# AUTOMATIC_WATER_PUMPS_V1.net
KiCad netlist of a schematic drawn in Altium Designer
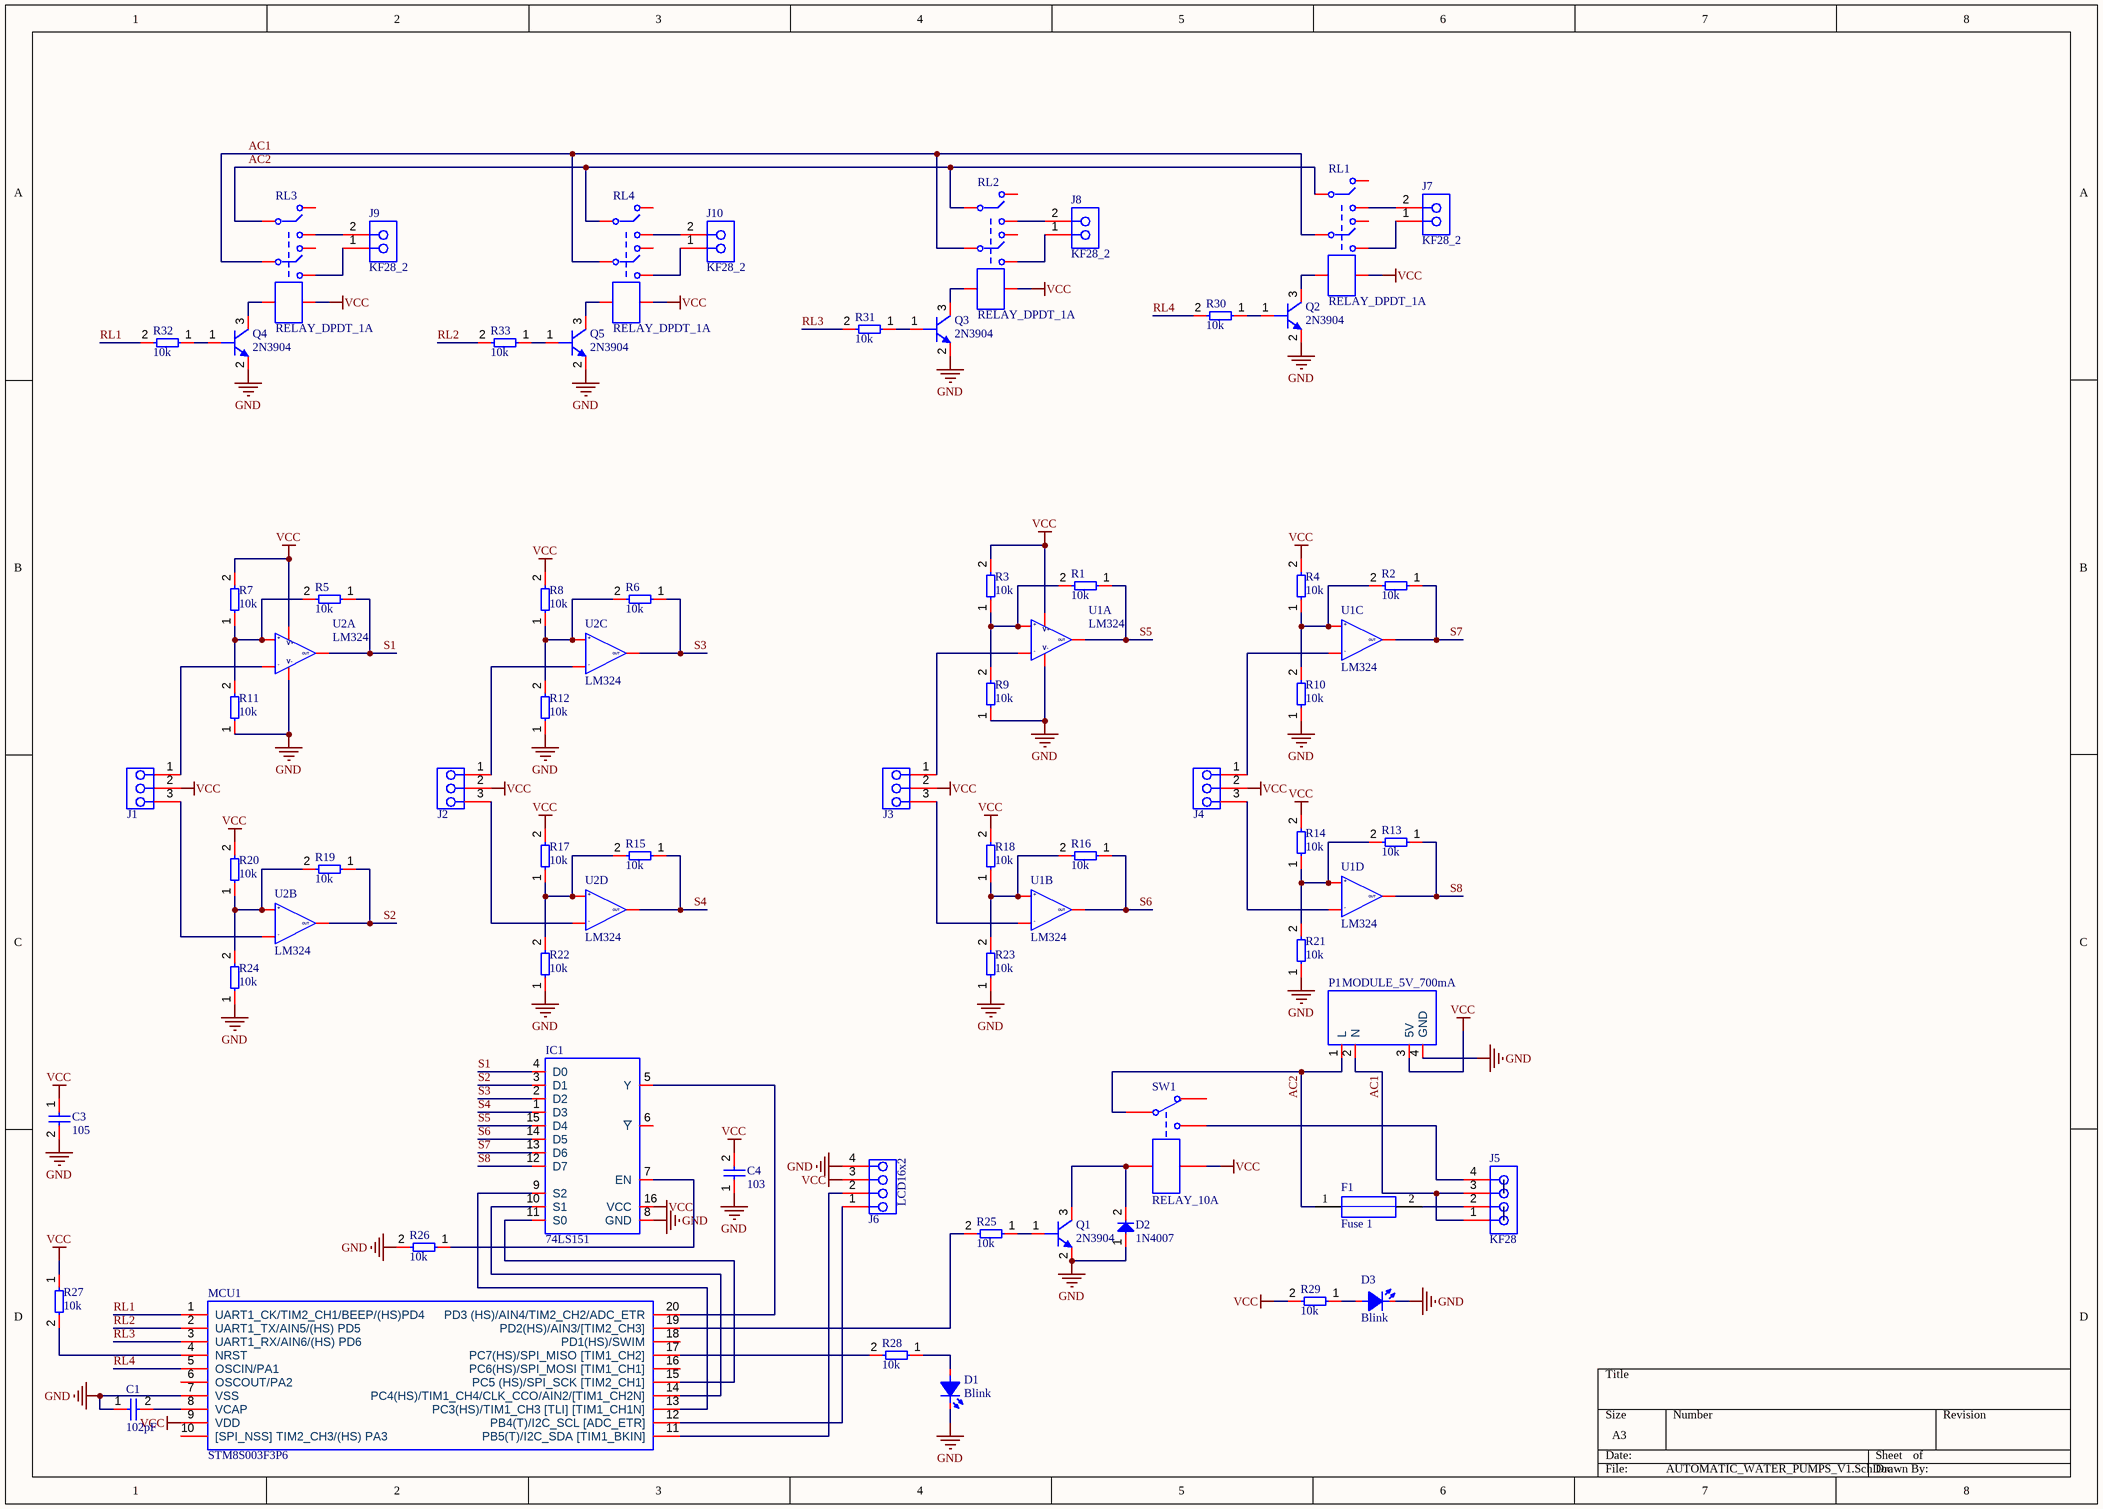
[diagram p0: AUTOMATIC_WATER_PUMPS_V1.SchDoc]

(export (version "E")
  (design (tool "Eeschema 10.0.6"))
  (components
    (comp (ref "C1")
      (value "102pF")
      (footprint "C0805")
      (libsource (lib "Lib31082020") (part "Capacitors(SMD)"))
    )
    (comp (ref "C3") (value "105") (footprint "C0805") (libsource (lib "Lib31082020") (part "C0805")))
    (comp (ref "C4") (value "103") (footprint "C0805") (libsource (lib "Lib31082020") (part "C0805")))
    (comp (ref "D1") (value "Blink") (footprint "L0805RED") (libsource (lib "Lib31082020") (part "LED0805")))
    (comp (ref "D2")
      (value "1N4007")
      (footprint "DO-214AC(SMA)")
      (libsource (lib "Lib31082020") (part "Diode 1N4007-DO214AC(SMA)"))
    )
    (comp (ref "D3") (value "Blink") (footprint "L0805RED") (libsource (lib "Lib31082020") (part "LED0805")))
    (comp (ref "F1")
      (value "Fuse 1")
      (footprint "FUSE2")
      (fields (field (name "PUBLISHER") "Altium Limited"))
      (libsource (lib "Library 3D") (part "Fuse 1"))
    )
    (comp (ref "IC1")
      (value "74LS151")
      (footprint "SOP16")
      (description "8-input multiplexer")
      (libsource (lib "Lib31082020") (part "74LS151"))
    )
    (comp (ref "J1")
      (value "WT1")
      (footprint "JST - XH - Thru (R) - 3Pin - 2.54mm")
      (libsource (lib "Lib31082020") (part "JST - XH - Thru (R) - 3Pin - 2.54mm"))
    )
    (comp (ref "J2")
      (value "WT2")
      (footprint "JST - XH - Thru (R) - 3Pin - 2.54mm")
      (libsource (lib "Lib31082020") (part "JST - XH - Thru (R) - 3Pin - 2.54mm"))
    )
    (comp (ref "J3")
      (value "WT3")
      (footprint "JST - XH - Thru (R) - 3Pin - 2.54mm")
      (libsource (lib "Lib31082020") (part "JST - XH - Thru (R) - 3Pin - 2.54mm"))
    )
    (comp (ref "J4")
      (value "WT4")
      (footprint "JST - XH - Thru (R) - 3Pin - 2.54mm")
      (libsource (lib "Lib31082020") (part "JST - XH - Thru (R) - 3Pin - 2.54mm"))
    )
    (comp (ref "J5")
      (value "KF28")
      (footprint "HEADER_KF128_4_5.08MM")
      (libsource (lib "Lib31082020") (part "HEADER_KF128_4_5.08MM"))
    )
    (comp (ref "J6")
      (value "LCD16x2")
      (footprint "JST - XH - Thru (R) - 4Pin - 2.54mm")
      (libsource (lib "Lib31082020") (part "JST - XH - Thru (R) - 4Pin - 2.54mm"))
    )
    (comp (ref "J7")
      (value "KF28_2")
      (footprint "HEADER_KF128_2_5.08MM")
      (libsource (lib "Lib31082020") (part "HEADER_KF128_2_5.08MM"))
    )
    (comp (ref "J8")
      (value "KF28_2")
      (footprint "HEADER_KF128_2_5.08MM")
      (libsource (lib "Lib31082020") (part "HEADER_KF128_2_5.08MM"))
    )
    (comp (ref "J9")
      (value "KF28_2")
      (footprint "HEADER_KF128_2_5.08MM")
      (libsource (lib "Lib31082020") (part "HEADER_KF128_2_5.08MM"))
    )
    (comp (ref "J10")
      (value "KF28_2")
      (footprint "HEADER_KF128_2_5.08MM")
      (libsource (lib "Lib31082020") (part "HEADER_KF128_2_5.08MM"))
    )
    (comp (ref "MCU1")
      (value "STM8S003F3P6")
      (footprint "TSSOP20_0.65_4.4")
      (libsource (lib "Lib31082020") (part "STM8S003F3P6"))
    )
    (comp (ref "P1")
      (value "MODULE_5V_700mA")
      (footprint "MODULE_5V_700mA")
      (libsource (lib "Lib31082020") (part "MODULE_5V_700mA"))
    )
    (comp (ref "Q1")
      (value "2N3904")
      (footprint "SOT23-3")
      (libsource (lib "Lib31082020") (part "2N3904 (SOT-23)"))
    )
    (comp (ref "Q2")
      (value "2N3904")
      (footprint "SOT23-3")
      (libsource (lib "Lib31082020") (part "2N3904 (SOT-23)"))
    )
    (comp (ref "Q3")
      (value "2N3904")
      (footprint "SOT23-3")
      (libsource (lib "Lib31082020") (part "2N3904 (SOT-23)"))
    )
    (comp (ref "Q4")
      (value "2N3904")
      (footprint "SOT23-3")
      (libsource (lib "Lib31082020") (part "2N3904 (SOT-23)"))
    )
    (comp (ref "Q5")
      (value "2N3904")
      (footprint "SOT23-3")
      (libsource (lib "Lib31082020") (part "2N3904 (SOT-23)"))
    )
    (comp (ref "R1") (value "10k") (footprint "R0805") (libsource (lib "Lib31082020") (part "Resistor SMD")))
    (comp (ref "R2") (value "10k") (footprint "R0805") (libsource (lib "Lib31082020") (part "Resistor SMD")))
    (comp (ref "R3") (value "10k") (footprint "R0805") (libsource (lib "") (part "Resistor SMD_1")))
    (comp (ref "R4") (value "10k") (footprint "R0805") (libsource (lib "") (part "Resistor SMD_1")))
    (comp (ref "R5") (value "10k") (footprint "R0805") (libsource (lib "Lib31082020") (part "Resistor SMD")))
    (comp (ref "R6") (value "10k") (footprint "R0805") (libsource (lib "Lib31082020") (part "Resistor SMD")))
    (comp (ref "R7") (value "10k") (footprint "R0805") (libsource (lib "") (part "Resistor SMD_1")))
    (comp (ref "R8") (value "10k") (footprint "R0805") (libsource (lib "") (part "Resistor SMD_1")))
    (comp (ref "R9") (value "10k") (footprint "R0805") (libsource (lib "") (part "Resistor SMD_1")))
    (comp (ref "R10") (value "10k") (footprint "R0805") (libsource (lib "") (part "Resistor SMD_1")))
    (comp (ref "R11") (value "10k") (footprint "R0805") (libsource (lib "") (part "Resistor SMD_1")))
    (comp (ref "R12") (value "10k") (footprint "R0805") (libsource (lib "") (part "Resistor SMD_1")))
    (comp (ref "R13") (value "10k") (footprint "R0805") (libsource (lib "Lib31082020") (part "Resistor SMD")))
    (comp (ref "R14") (value "10k") (footprint "R0805") (libsource (lib "") (part "Resistor SMD_1")))
    (comp (ref "R15") (value "10k") (footprint "R0805") (libsource (lib "Lib31082020") (part "Resistor SMD")))
    (comp (ref "R16") (value "10k") (footprint "R0805") (libsource (lib "Lib31082020") (part "Resistor SMD")))
    (comp (ref "R17") (value "10k") (footprint "R0805") (libsource (lib "") (part "Resistor SMD_1")))
    (comp (ref "R18") (value "10k") (footprint "R0805") (libsource (lib "") (part "Resistor SMD_1")))
    (comp (ref "R19") (value "10k") (footprint "R0805") (libsource (lib "Lib31082020") (part "Resistor SMD")))
    (comp (ref "R20") (value "10k") (footprint "R0805") (libsource (lib "") (part "Resistor SMD_1")))
    (comp (ref "R21") (value "10k") (footprint "R0805") (libsource (lib "") (part "Resistor SMD_1")))
    (comp (ref "R22") (value "10k") (footprint "R0805") (libsource (lib "") (part "Resistor SMD_1")))
    (comp (ref "R23") (value "10k") (footprint "R0805") (libsource (lib "") (part "Resistor SMD_1")))
    (comp (ref "R24") (value "10k") (footprint "R0805") (libsource (lib "") (part "Resistor SMD_1")))
    (comp (ref "R25") (value "10k") (footprint "R0805") (libsource (lib "Lib31082020") (part "Resistor SMD")))
    (comp (ref "R26") (value "10k") (footprint "R0805") (libsource (lib "Lib31082020") (part "Resistor SMD")))
    (comp (ref "R27") (value "10k") (footprint "R0805") (libsource (lib "") (part "Resistor SMD_2")))
    (comp (ref "R28") (value "10k") (footprint "R0805") (libsource (lib "Lib31082020") (part "Resistor SMD")))
    (comp (ref "R29") (value "10k") (footprint "R0805") (libsource (lib "Lib31082020") (part "Resistor SMD")))
    (comp (ref "R30") (value "10k") (footprint "R0805") (libsource (lib "Lib31082020") (part "Resistor SMD")))
    (comp (ref "R31") (value "10k") (footprint "R0805") (libsource (lib "Lib31082020") (part "Resistor SMD")))
    (comp (ref "R32") (value "10k") (footprint "R0805") (libsource (lib "Lib31082020") (part "Resistor SMD")))
    (comp (ref "R33") (value "10k") (footprint "R0805") (libsource (lib "Lib31082020") (part "Resistor SMD")))
    (comp (ref "RL1")
      (value "RELAY_DPDT_1A")
      (footprint "RELAY_DPDT_1A")
      (libsource (lib "Lib31082020") (part "RELAY_DPDT_1A"))
    )
    (comp (ref "RL2")
      (value "RELAY_DPDT_1A")
      (footprint "RELAY_DPDT_1A")
      (libsource (lib "Lib31082020") (part "RELAY_DPDT_1A"))
    )
    (comp (ref "RL3")
      (value "RELAY_DPDT_1A")
      (footprint "RELAY_DPDT_1A")
      (libsource (lib "Lib31082020") (part "RELAY_DPDT_1A"))
    )
    (comp (ref "RL4")
      (value "RELAY_DPDT_1A")
      (footprint "RELAY_DPDT_1A")
      (libsource (lib "Lib31082020") (part "RELAY_DPDT_1A"))
    )
    (comp (ref "SW1")
      (value "RELAY_10A")
      (footprint "RELAY_10A_5PIN")
      (libsource (lib "Lib31082020") (part "RELAY_10A"))
    )
    (comp (ref "U1")
      (value "LM324")
      (footprint "SOP-14")
      (description "Quad-Operational Amp")
      (libsource (lib "Lib31082020") (part "LM324"))
    )
    (comp (ref "U2")
      (value "LM324")
      (footprint "SOP-14")
      (description "Quad-Operational Amp")
      (libsource (lib "Lib31082020") (part "LM324"))
    )
  )
  (nets
    (net (code "1") (name "/AC1") (class "Default")
      (node (ref "J5") (pin "1") (pinfunction "1_1") (pintype "passive"))
      (node (ref "J5") (pin "3") (pinfunction "3_3") (pintype "passive"))
      (node (ref "P1") (pin "2") (pinfunction "N_2") (pintype "passive"))
      (node (ref "RL1") (pin "5") (pinfunction "5_5") (pintype "passive"))
      (node (ref "RL2") (pin "5") (pinfunction "5_5") (pintype "passive"))
      (node (ref "RL3") (pin "5") (pinfunction "5_5") (pintype "passive"))
      (node (ref "RL4") (pin "5") (pinfunction "5_5") (pintype "passive"))
    )
    (net (code "2") (name "/AC2") (class "Default")
      (node (ref "F1") (pin "1") (pinfunction "1_1") (pintype "passive"))
      (node (ref "P1") (pin "1") (pinfunction "L_1") (pintype "passive"))
      (node (ref "RL1") (pin "2") (pinfunction "2_2") (pintype "passive"))
      (node (ref "RL2") (pin "2") (pinfunction "2_2") (pintype "passive"))
      (node (ref "RL3") (pin "2") (pinfunction "2_2") (pintype "passive"))
      (node (ref "RL4") (pin "2") (pinfunction "2_2") (pintype "passive"))
      (node (ref "SW1") (pin "2") (pinfunction "2_2") (pintype "passive"))
    )
    (net (code "3") (name "/RL1") (class "Default")
      (node (ref "MCU1") (pin "1") (pinfunction "UART1_CK/TIM2_CH1/BEEP/(HS)PD4_1") (pintype "passive"))
      (node (ref "R32") (pin "2") (pinfunction "2_2") (pintype "passive"))
    )
    (net (code "4") (name "/RL2") (class "Default")
      (node (ref "MCU1") (pin "2") (pinfunction "UART1_TX/AIN5/(HS)_PD5_2") (pintype "passive"))
      (node (ref "R33") (pin "2") (pinfunction "2_2") (pintype "passive"))
    )
    (net (code "5") (name "/RL3") (class "Default")
      (node (ref "MCU1") (pin "3") (pinfunction "UART1_RX/AIN6/(HS)_PD6_3") (pintype "passive"))
      (node (ref "R31") (pin "2") (pinfunction "2_2") (pintype "passive"))
    )
    (net (code "6") (name "/RL4") (class "Default")
      (node (ref "MCU1") (pin "5") (pinfunction "OSCIN/PA1_5") (pintype "passive"))
      (node (ref "R30") (pin "2") (pinfunction "2_2") (pintype "passive"))
    )
    (net (code "7") (name "/S1") (class "Default")
      (node (ref "IC1") (pin "4") (pinfunction "D0_4") (pintype "passive"))
      (node (ref "R5") (pin "1") (pinfunction "1_1") (pintype "passive"))
      (node (ref "U2") (pin "1") (pinfunction "OUT_1") (pintype "passive"))
    )
    (net (code "8") (name "/S2") (class "Default")
      (node (ref "IC1") (pin "3") (pinfunction "D1_3") (pintype "passive"))
      (node (ref "R19") (pin "1") (pinfunction "1_1") (pintype "passive"))
      (node (ref "U2") (pin "7") (pinfunction "OUT_7") (pintype "passive"))
    )
    (net (code "9") (name "/S3") (class "Default")
      (node (ref "IC1") (pin "2") (pinfunction "D2_2") (pintype "passive"))
      (node (ref "R6") (pin "1") (pinfunction "1_1") (pintype "passive"))
      (node (ref "U2") (pin "8") (pinfunction "OUT_8") (pintype "passive"))
    )
    (net (code "10") (name "/S4") (class "Default")
      (node (ref "IC1") (pin "1") (pinfunction "D3_1") (pintype "passive"))
      (node (ref "R15") (pin "1") (pinfunction "1_1") (pintype "passive"))
      (node (ref "U2") (pin "14") (pinfunction "OUT_14") (pintype "passive"))
    )
    (net (code "11") (name "/S5") (class "Default")
      (node (ref "IC1") (pin "15") (pinfunction "D4_15") (pintype "passive"))
      (node (ref "R1") (pin "1") (pinfunction "1_1") (pintype "passive"))
      (node (ref "U1") (pin "1") (pinfunction "OUT_1") (pintype "passive"))
    )
    (net (code "12") (name "/S6") (class "Default")
      (node (ref "IC1") (pin "14") (pinfunction "D5_14") (pintype "passive"))
      (node (ref "R16") (pin "1") (pinfunction "1_1") (pintype "passive"))
      (node (ref "U1") (pin "7") (pinfunction "OUT_7") (pintype "passive"))
    )
    (net (code "13") (name "/S7") (class "Default")
      (node (ref "IC1") (pin "13") (pinfunction "D6_13") (pintype "passive"))
      (node (ref "R2") (pin "1") (pinfunction "1_1") (pintype "passive"))
      (node (ref "U1") (pin "8") (pinfunction "OUT_8") (pintype "passive"))
    )
    (net (code "14") (name "/S8") (class "Default")
      (node (ref "IC1") (pin "12") (pinfunction "D7_12") (pintype "passive"))
      (node (ref "R13") (pin "1") (pinfunction "1_1") (pintype "passive"))
      (node (ref "U1") (pin "14") (pinfunction "OUT_14") (pintype "passive"))
    )
    (net (code "15") (name "GND") (class "Default")
      (node (ref "C1") (pin "1") (pinfunction "1_1") (pintype "passive"))
      (node (ref "C3") (pin "2") (pinfunction "2_2") (pintype "passive"))
      (node (ref "C4") (pin "1") (pinfunction "1_1") (pintype "passive"))
      (node (ref "D1") (pin "2") (pinfunction "K_2") (pintype "passive"))
      (node (ref "D2") (pin "1") (pinfunction "1_1") (pintype "passive"))
      (node (ref "D3") (pin "2") (pinfunction "K_2") (pintype "passive"))
      (node (ref "IC1") (pin "8") (pinfunction "GND_8") (pintype "passive"))
      (node (ref "J6") (pin "4") (pinfunction "4_4") (pintype "passive"))
      (node (ref "MCU1") (pin "7") (pinfunction "VSS_7") (pintype "passive"))
      (node (ref "P1") (pin "4") (pinfunction "GND_4") (pintype "passive"))
      (node (ref "Q1") (pin "2") (pinfunction "E_2") (pintype "passive"))
      (node (ref "Q2") (pin "2") (pinfunction "E_2") (pintype "passive"))
      (node (ref "Q3") (pin "2") (pinfunction "E_2") (pintype "passive"))
      (node (ref "Q4") (pin "2") (pinfunction "E_2") (pintype "passive"))
      (node (ref "Q5") (pin "2") (pinfunction "E_2") (pintype "passive"))
      (node (ref "R10") (pin "1") (pinfunction "1_1") (pintype "passive"))
      (node (ref "R11") (pin "1") (pinfunction "1_1") (pintype "passive"))
      (node (ref "R12") (pin "1") (pinfunction "1_1") (pintype "passive"))
      (node (ref "R21") (pin "1") (pinfunction "1_1") (pintype "passive"))
      (node (ref "R22") (pin "1") (pinfunction "1_1") (pintype "passive"))
      (node (ref "R23") (pin "1") (pinfunction "1_1") (pintype "passive"))
      (node (ref "R24") (pin "1") (pinfunction "1_1") (pintype "passive"))
      (node (ref "R26") (pin "2") (pinfunction "2_2") (pintype "passive"))
      (node (ref "R9") (pin "1") (pinfunction "1_1") (pintype "passive"))
      (node (ref "U1") (pin "11") (pinfunction "11_11") (pintype "power_in"))
      (node (ref "U2") (pin "11") (pinfunction "11_11") (pintype "power_in"))
    )
    (net (code "16") (name "Net-(D1-A)") (class "Default")
      (node (ref "D1") (pin "1") (pinfunction "A_1") (pintype "passive"))
      (node (ref "R28") (pin "1") (pinfunction "1_1") (pintype "passive"))
    )
    (net (code "17") (name "Net-(D3-A)") (class "Default")
      (node (ref "D3") (pin "1") (pinfunction "A_1") (pintype "passive"))
      (node (ref "R29") (pin "1") (pinfunction "1_1") (pintype "passive"))
    )
    (net (code "18") (name "Net-(F1-Pad2)") (class "Default")
      (node (ref "F1") (pin "2") (pinfunction "2_2") (pintype "passive"))
      (node (ref "J5") (pin "2") (pinfunction "2_2") (pintype "passive"))
    )
    (net (code "19") (name "Net-(IC1-EN)") (class "Default")
      (node (ref "IC1") (pin "7") (pinfunction "EN_7") (pintype "passive"))
      (node (ref "R26") (pin "1") (pinfunction "1_1") (pintype "passive"))
    )
    (net (code "20") (name "Net-(IC1-S0)") (class "Default")
      (node (ref "IC1") (pin "11") (pinfunction "S0_11") (pintype "passive"))
      (node (ref "MCU1") (pin "15") (pinfunction "PC5_(HS)/SPI_SCK_[TIM2_CH1]_15") (pintype "passive"))
    )
    (net (code "21") (name "Net-(IC1-S1)") (class "Default")
      (node (ref "IC1") (pin "10") (pinfunction "S1_10") (pintype "passive"))
      (node (ref "MCU1") (pin "14") (pinfunction "PC4(HS)/TIM1_CH4/CLK_CCO/AIN2/[TIM1_CH2N]_14") (pintype "passive"))
    )
    (net (code "22") (name "Net-(IC1-S2)") (class "Default")
      (node (ref "IC1") (pin "9") (pinfunction "S2_9") (pintype "passive"))
      (node (ref "MCU1") (pin "13") (pinfunction "PC3(HS)/TIM1_CH3_[TLI]_[TIM1_CH1N]_13") (pintype "passive"))
    )
    (net (code "23") (name "Net-(IC1-Y)") (class "Default")
      (node (ref "IC1") (pin "5") (pinfunction "Y_5") (pintype "passive"))
      (node (ref "MCU1") (pin "20") (pinfunction "PD3_(HS)/AIN4/TIM2_CH2/ADC_ETR_20") (pintype "passive"))
    )
    (net (code "24") (name "Net-(J5-Pad4)") (class "Default")
      (node (ref "J5") (pin "4") (pinfunction "4_4") (pintype "passive"))
      (node (ref "SW1") (pin "5") (pinfunction "5_5") (pintype "passive"))
    )
    (net (code "25") (name "Net-(J7-Pad1)") (class "Default")
      (node (ref "J7") (pin "1") (pinfunction "1_1") (pintype "passive"))
      (node (ref "RL1") (pin "6") (pinfunction "6_6") (pintype "passive"))
    )
    (net (code "26") (name "Net-(J7-Pad2)") (class "Default")
      (node (ref "J7") (pin "2") (pinfunction "2_2") (pintype "passive"))
      (node (ref "RL1") (pin "3") (pinfunction "3_3") (pintype "passive"))
    )
    (net (code "27") (name "Net-(J8-Pad1)") (class "Default")
      (node (ref "J8") (pin "1") (pinfunction "1_1") (pintype "passive"))
      (node (ref "RL2") (pin "6") (pinfunction "6_6") (pintype "passive"))
    )
    (net (code "28") (name "Net-(J8-Pad2)") (class "Default")
      (node (ref "J8") (pin "2") (pinfunction "2_2") (pintype "passive"))
      (node (ref "RL2") (pin "3") (pinfunction "3_3") (pintype "passive"))
    )
    (net (code "29") (name "Net-(J9-Pad1)") (class "Default")
      (node (ref "J9") (pin "1") (pinfunction "1_1") (pintype "passive"))
      (node (ref "RL3") (pin "6") (pinfunction "6_6") (pintype "passive"))
    )
    (net (code "30") (name "Net-(J9-Pad2)") (class "Default")
      (node (ref "J9") (pin "2") (pinfunction "2_2") (pintype "passive"))
      (node (ref "RL3") (pin "3") (pinfunction "3_3") (pintype "passive"))
    )
    (net (code "31") (name "Net-(J10-Pad1)") (class "Default")
      (node (ref "J10") (pin "1") (pinfunction "1_1") (pintype "passive"))
      (node (ref "RL4") (pin "6") (pinfunction "6_6") (pintype "passive"))
    )
    (net (code "32") (name "Net-(J10-Pad2)") (class "Default")
      (node (ref "J10") (pin "2") (pinfunction "2_2") (pintype "passive"))
      (node (ref "RL4") (pin "3") (pinfunction "3_3") (pintype "passive"))
    )
    (net (code "33") (name "Net-(MCU1-NRST)") (class "Default")
      (node (ref "MCU1") (pin "4") (pinfunction "NRST_4") (pintype "passive"))
      (node (ref "R27") (pin "2") (pinfunction "2_2") (pintype "passive"))
    )
    (net (code "34") (name "Net-(MCU1-PB4(T){slash}I2C_SCL_[ADC_ETR])") (class "Default")
      (node (ref "J6") (pin "1") (pinfunction "1_1") (pintype "passive"))
      (node (ref "MCU1") (pin "12") (pinfunction "PB4(T)/I2C_SCL_[ADC_ETR]_12") (pintype "passive"))
    )
    (net (code "35") (name "Net-(MCU1-PB5(T){slash}I2C_SDA_[TIM1_BKIN])") (class "Default")
      (node (ref "J6") (pin "2") (pinfunction "2_2") (pintype "passive"))
      (node (ref "MCU1") (pin "11") (pinfunction "PB5(T)/I2C_SDA_[TIM1_BKIN]_11") (pintype "passive"))
    )
    (net (code "36") (name "Net-(MCU1-PC7(HS){slash}SPI_MISO_[TIM1_CH2])") (class "Default")
      (node (ref "MCU1") (pin "17") (pinfunction "PC7(HS)/SPI_MISO_[TIM1_CH2]_17") (pintype "passive"))
      (node (ref "R28") (pin "2") (pinfunction "2_2") (pintype "passive"))
    )
    (net (code "37") (name "Net-(MCU1-PD2(HS){slash}AIN3{slash}[TIM2_CH3])") (class "Default")
      (node (ref "MCU1") (pin "19") (pinfunction "PD2(HS)/AIN3/[TIM2_CH3]_19") (pintype "passive"))
      (node (ref "R25") (pin "2") (pinfunction "2_2") (pintype "passive"))
    )
    (net (code "38") (name "Net-(MCU1-VCAP)") (class "Default")
      (node (ref "C1") (pin "2") (pinfunction "2_2") (pintype "passive"))
      (node (ref "MCU1") (pin "8") (pinfunction "VCAP_8") (pintype "passive"))
    )
    (net (code "39") (name "Net-(Q1-B)") (class "Default")
      (node (ref "Q1") (pin "1") (pinfunction "B_1") (pintype "passive"))
      (node (ref "R25") (pin "1") (pinfunction "1_1") (pintype "passive"))
    )
    (net (code "40") (name "Net-(Q1-C)") (class "Default")
      (node (ref "D2") (pin "2") (pinfunction "2_2") (pintype "passive"))
      (node (ref "Q1") (pin "3") (pinfunction "C_3") (pintype "passive"))
      (node (ref "SW1") (pin "1") (pinfunction "1_1") (pintype "passive"))
    )
    (net (code "41") (name "Net-(Q2-B)") (class "Default")
      (node (ref "Q2") (pin "1") (pinfunction "B_1") (pintype "passive"))
      (node (ref "R30") (pin "1") (pinfunction "1_1") (pintype "passive"))
    )
    (net (code "42") (name "Net-(Q2-C)") (class "Default")
      (node (ref "Q2") (pin "3") (pinfunction "C_3") (pintype "passive"))
      (node (ref "RL1") (pin "7") (pinfunction "7_7") (pintype "passive"))
    )
    (net (code "43") (name "Net-(Q3-B)") (class "Default")
      (node (ref "Q3") (pin "1") (pinfunction "B_1") (pintype "passive"))
      (node (ref "R31") (pin "1") (pinfunction "1_1") (pintype "passive"))
    )
    (net (code "44") (name "Net-(Q3-C)") (class "Default")
      (node (ref "Q3") (pin "3") (pinfunction "C_3") (pintype "passive"))
      (node (ref "RL2") (pin "7") (pinfunction "7_7") (pintype "passive"))
    )
    (net (code "45") (name "Net-(Q4-B)") (class "Default")
      (node (ref "Q4") (pin "1") (pinfunction "B_1") (pintype "passive"))
      (node (ref "R32") (pin "1") (pinfunction "1_1") (pintype "passive"))
    )
    (net (code "46") (name "Net-(Q4-C)") (class "Default")
      (node (ref "Q4") (pin "3") (pinfunction "C_3") (pintype "passive"))
      (node (ref "RL3") (pin "7") (pinfunction "7_7") (pintype "passive"))
    )
    (net (code "47") (name "Net-(Q5-B)") (class "Default")
      (node (ref "Q5") (pin "1") (pinfunction "B_1") (pintype "passive"))
      (node (ref "R33") (pin "1") (pinfunction "1_1") (pintype "passive"))
    )
    (net (code "48") (name "Net-(Q5-C)") (class "Default")
      (node (ref "Q5") (pin "3") (pinfunction "C_3") (pintype "passive"))
      (node (ref "RL4") (pin "7") (pinfunction "7_7") (pintype "passive"))
    )
    (net (code "49") (name "Net-(R16-Pad2)") (class "Default")
      (node (ref "R16") (pin "2") (pinfunction "2_2") (pintype "passive"))
      (node (ref "R18") (pin "1") (pinfunction "1_1") (pintype "passive"))
      (node (ref "R23") (pin "2") (pinfunction "2_2") (pintype "passive"))
      (node (ref "U1") (pin "5") (pinfunction "5_5") (pintype "passive"))
    )
    (net (code "50") (name "Net-(R19-Pad2)") (class "Default")
      (node (ref "R19") (pin "2") (pinfunction "2_2") (pintype "passive"))
      (node (ref "R20") (pin "1") (pinfunction "1_1") (pintype "passive"))
      (node (ref "R24") (pin "2") (pinfunction "2_2") (pintype "passive"))
      (node (ref "U2") (pin "5") (pinfunction "5_5") (pintype "passive"))
    )
    (net (code "51") (name "Net-(U1A-+)") (class "Default")
      (node (ref "R1") (pin "2") (pinfunction "2_2") (pintype "passive"))
      (node (ref "R3") (pin "1") (pinfunction "1_1") (pintype "passive"))
      (node (ref "R9") (pin "2") (pinfunction "2_2") (pintype "passive"))
      (node (ref "U1") (pin "3") (pinfunction "+_3") (pintype "passive"))
    )
    (net (code "52") (name "Net-(U1A--)") (class "Default")
      (node (ref "J3") (pin "1") (pinfunction "1_1") (pintype "passive"))
      (node (ref "U1") (pin "2") (pinfunction "-_2") (pintype "passive"))
    )
    (net (code "53") (name "Net-(U1B--)") (class "Default")
      (node (ref "J3") (pin "3") (pinfunction "3_3") (pintype "passive"))
      (node (ref "U1") (pin "6") (pinfunction "-_6") (pintype "passive"))
    )
    (net (code "54") (name "Net-(U1C-+)") (class "Default")
      (node (ref "R10") (pin "2") (pinfunction "2_2") (pintype "passive"))
      (node (ref "R2") (pin "2") (pinfunction "2_2") (pintype "passive"))
      (node (ref "R4") (pin "1") (pinfunction "1_1") (pintype "passive"))
      (node (ref "U1") (pin "10") (pinfunction "+_10") (pintype "passive"))
    )
    (net (code "55") (name "Net-(U1C--)") (class "Default")
      (node (ref "J4") (pin "1") (pinfunction "1_1") (pintype "passive"))
      (node (ref "U1") (pin "9") (pinfunction "-_9") (pintype "passive"))
    )
    (net (code "56") (name "Net-(U1D-+)") (class "Default")
      (node (ref "R13") (pin "2") (pinfunction "2_2") (pintype "passive"))
      (node (ref "R14") (pin "1") (pinfunction "1_1") (pintype "passive"))
      (node (ref "R21") (pin "2") (pinfunction "2_2") (pintype "passive"))
      (node (ref "U1") (pin "12") (pinfunction "+_12") (pintype "passive"))
    )
    (net (code "57") (name "Net-(U1D--)") (class "Default")
      (node (ref "J4") (pin "3") (pinfunction "3_3") (pintype "passive"))
      (node (ref "U1") (pin "13") (pinfunction "-_13") (pintype "passive"))
    )
    (net (code "58") (name "Net-(U2A-+)") (class "Default")
      (node (ref "R11") (pin "2") (pinfunction "2_2") (pintype "passive"))
      (node (ref "R5") (pin "2") (pinfunction "2_2") (pintype "passive"))
      (node (ref "R7") (pin "1") (pinfunction "1_1") (pintype "passive"))
      (node (ref "U2") (pin "3") (pinfunction "+_3") (pintype "passive"))
    )
    (net (code "59") (name "Net-(U2A--)") (class "Default")
      (node (ref "J1") (pin "1") (pinfunction "1_1") (pintype "passive"))
      (node (ref "U2") (pin "2") (pinfunction "-_2") (pintype "passive"))
    )
    (net (code "60") (name "Net-(U2B--)") (class "Default")
      (node (ref "J1") (pin "3") (pinfunction "3_3") (pintype "passive"))
      (node (ref "U2") (pin "6") (pinfunction "-_6") (pintype "passive"))
    )
    (net (code "61") (name "Net-(U2C-+)") (class "Default")
      (node (ref "R12") (pin "2") (pinfunction "2_2") (pintype "passive"))
      (node (ref "R6") (pin "2") (pinfunction "2_2") (pintype "passive"))
      (node (ref "R8") (pin "1") (pinfunction "1_1") (pintype "passive"))
      (node (ref "U2") (pin "10") (pinfunction "+_10") (pintype "passive"))
    )
    (net (code "62") (name "Net-(U2C--)") (class "Default")
      (node (ref "J2") (pin "1") (pinfunction "1_1") (pintype "passive"))
      (node (ref "U2") (pin "9") (pinfunction "-_9") (pintype "passive"))
    )
    (net (code "63") (name "Net-(U2D-+)") (class "Default")
      (node (ref "R15") (pin "2") (pinfunction "2_2") (pintype "passive"))
      (node (ref "R17") (pin "1") (pinfunction "1_1") (pintype "passive"))
      (node (ref "R22") (pin "2") (pinfunction "2_2") (pintype "passive"))
      (node (ref "U2") (pin "12") (pinfunction "+_12") (pintype "passive"))
    )
    (net (code "64") (name "Net-(U2D--)") (class "Default")
      (node (ref "J2") (pin "3") (pinfunction "3_3") (pintype "passive"))
      (node (ref "U2") (pin "13") (pinfunction "-_13") (pintype "passive"))
    )
    (net (code "65") (name "VCC") (class "Default")
      (node (ref "C3") (pin "1") (pinfunction "1_1") (pintype "passive"))
      (node (ref "C4") (pin "2") (pinfunction "2_2") (pintype "passive"))
      (node (ref "IC1") (pin "16") (pinfunction "VCC_16") (pintype "passive"))
      (node (ref "J1") (pin "2") (pinfunction "2_2") (pintype "passive"))
      (node (ref "J2") (pin "2") (pinfunction "2_2") (pintype "passive"))
      (node (ref "J3") (pin "2") (pinfunction "2_2") (pintype "passive"))
      (node (ref "J4") (pin "2") (pinfunction "2_2") (pintype "passive"))
      (node (ref "J6") (pin "3") (pinfunction "3_3") (pintype "passive"))
      (node (ref "MCU1") (pin "9") (pinfunction "VDD_9") (pintype "passive"))
      (node (ref "P1") (pin "3") (pinfunction "5V_3") (pintype "passive"))
      (node (ref "R14") (pin "2") (pinfunction "2_2") (pintype "passive"))
      (node (ref "R17") (pin "2") (pinfunction "2_2") (pintype "passive"))
      (node (ref "R18") (pin "2") (pinfunction "2_2") (pintype "passive"))
      (node (ref "R20") (pin "2") (pinfunction "2_2") (pintype "passive"))
      (node (ref "R27") (pin "1") (pinfunction "1_1") (pintype "passive"))
      (node (ref "R29") (pin "2") (pinfunction "2_2") (pintype "passive"))
      (node (ref "R3") (pin "2") (pinfunction "2_2") (pintype "passive"))
      (node (ref "R4") (pin "2") (pinfunction "2_2") (pintype "passive"))
      (node (ref "R7") (pin "2") (pinfunction "2_2") (pintype "passive"))
      (node (ref "R8") (pin "2") (pinfunction "2_2") (pintype "passive"))
      (node (ref "RL1") (pin "8") (pinfunction "8_8") (pintype "passive"))
      (node (ref "RL2") (pin "8") (pinfunction "8_8") (pintype "passive"))
      (node (ref "RL3") (pin "8") (pinfunction "8_8") (pintype "passive"))
      (node (ref "RL4") (pin "8") (pinfunction "8_8") (pintype "passive"))
      (node (ref "SW1") (pin "3") (pinfunction "3_3") (pintype "passive"))
      (node (ref "U1") (pin "4") (pinfunction "4_4") (pintype "power_in"))
      (node (ref "U2") (pin "4") (pinfunction "4_4") (pintype "power_in"))
    )
    (net (code "66") (name "unconnected-(IC1-~{Y}-Pad6)") (class "Default")
      (node (ref "IC1") (pin "6") (pinfunction "~{Y}_6") (pintype "passive"))
    )
    (net (code "67") (name "unconnected-(MCU1-OSCOUT{slash}PA2-Pad6)") (class "Default")
      (node (ref "MCU1") (pin "6") (pinfunction "OSCOUT/PA2_6") (pintype "passive"))
    )
    (net (code "68") (name "unconnected-(MCU1-PC6(HS){slash}SPI_MOSI_[TIM1_CH1]-Pad16)") (class "Default")
      (node (ref "MCU1") (pin "16") (pinfunction "PC6(HS)/SPI_MOSI_[TIM1_CH1]_16") (pintype "passive"))
    )
    (net (code "69") (name "unconnected-(MCU1-PD1(HS){slash}SWIM-Pad18)") (class "Default")
      (node (ref "MCU1") (pin "18") (pinfunction "PD1(HS)/SWIM_18") (pintype "passive"))
    )
    (net (code "70") (name "unconnected-(MCU1-[SPI_NSS]_TIM2_CH3{slash}(HS)_PA3-Pad10)") (class "Default")
      (node (ref "MCU1") (pin "10") (pinfunction "[SPI_NSS]_TIM2_CH3/(HS)_PA3_10") (pintype "passive"))
    )
    (net (code "71") (name "unconnected-(RL1-Pad1)") (class "Default")
      (node (ref "RL1") (pin "1") (pinfunction "1_1") (pintype "passive"))
    )
    (net (code "72") (name "unconnected-(RL1-Pad4)") (class "Default")
      (node (ref "RL1") (pin "4") (pinfunction "4_4") (pintype "passive"))
    )
    (net (code "73") (name "unconnected-(RL2-Pad1)") (class "Default")
      (node (ref "RL2") (pin "1") (pinfunction "1_1") (pintype "passive"))
    )
    (net (code "74") (name "unconnected-(RL2-Pad4)") (class "Default")
      (node (ref "RL2") (pin "4") (pinfunction "4_4") (pintype "passive"))
    )
    (net (code "75") (name "unconnected-(RL3-Pad1)") (class "Default")
      (node (ref "RL3") (pin "1") (pinfunction "1_1") (pintype "passive"))
    )
    (net (code "76") (name "unconnected-(RL3-Pad4)") (class "Default")
      (node (ref "RL3") (pin "4") (pinfunction "4_4") (pintype "passive"))
    )
    (net (code "77") (name "unconnected-(RL4-Pad1)") (class "Default")
      (node (ref "RL4") (pin "1") (pinfunction "1_1") (pintype "passive"))
    )
    (net (code "78") (name "unconnected-(RL4-Pad4)") (class "Default")
      (node (ref "RL4") (pin "4") (pinfunction "4_4") (pintype "passive"))
    )
    (net (code "79") (name "unconnected-(SW1-Pad4)") (class "Default")
      (node (ref "SW1") (pin "4") (pinfunction "4_4") (pintype "passive"))
    )
  )
)
